# Electronics_Schematic.net
KiCad netlist of a schematic drawn in EAGLE
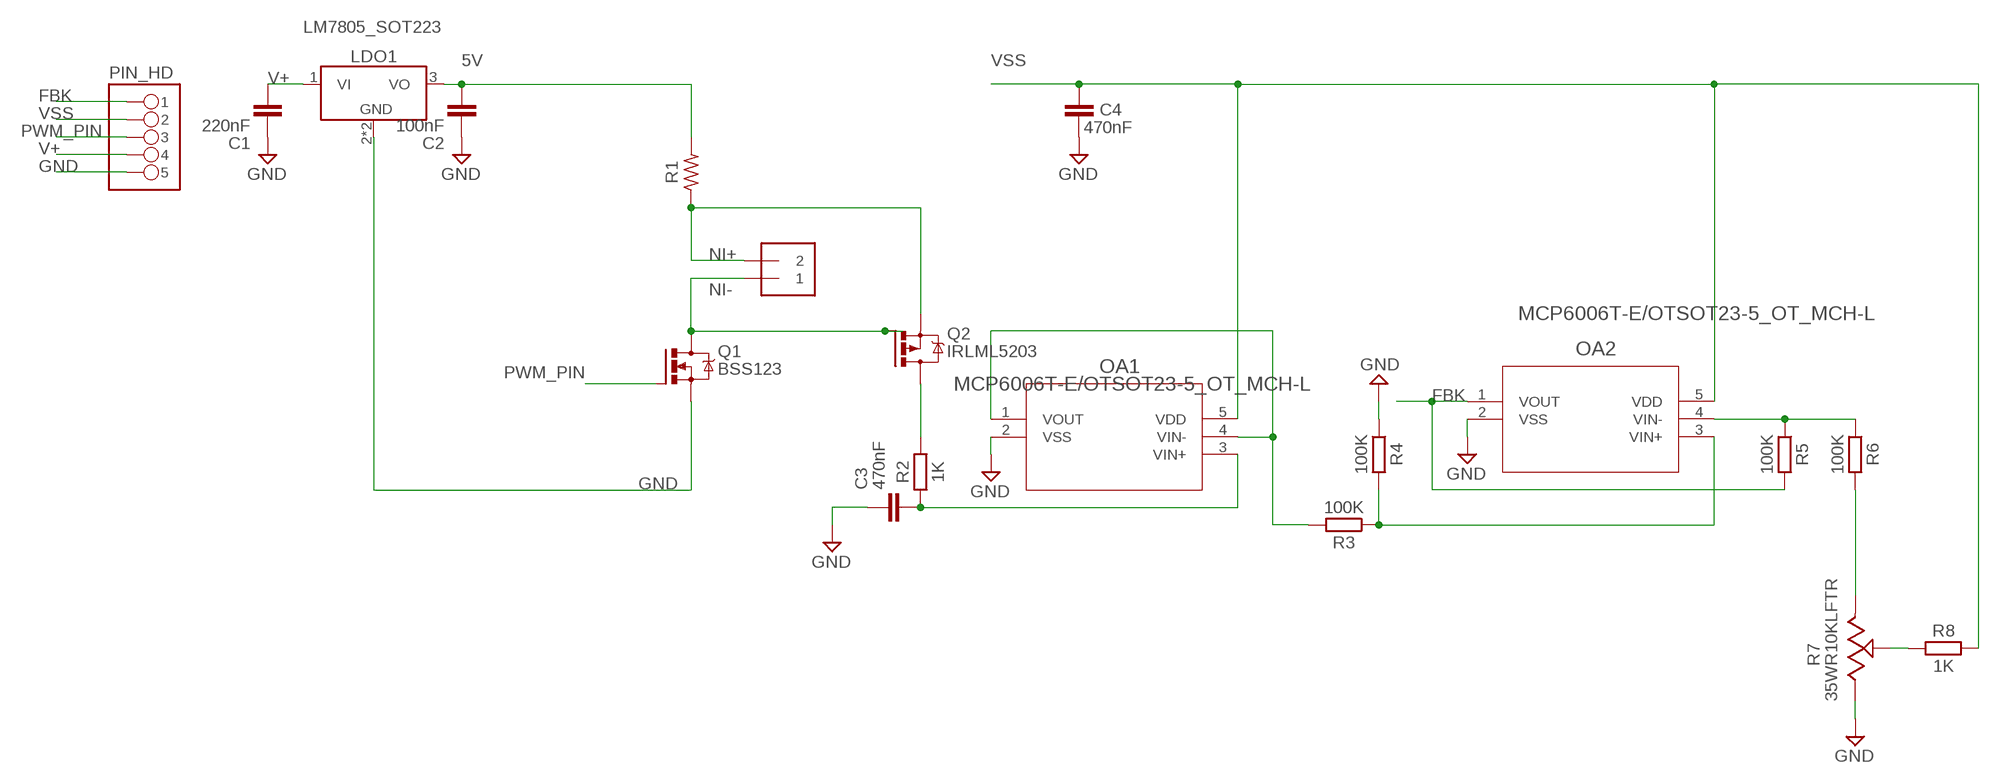
[diagram p0: schematic, sheet 1]

(export (version "E")
  (design (tool "Eeschema 10.0.6"))
  (components
    (comp (ref "C1")
      (value "220nF")
      (footprint "eagle-import:CAPC1005X60")
      (libsource (lib "eagle-import") (part "CCHIP-0402(1005-METRIC)_"))
    )
    (comp (ref "C2")
      (value "100nF")
      (footprint "eagle-import:CAPC1005X60")
      (libsource (lib "eagle-import") (part "CCHIP-0402(1005-METRIC)_"))
    )
    (comp (ref "C3")
      (value "470nF")
      (footprint "eagle-import:CAPC1005X60")
      (libsource (lib "eagle-import") (part "CCHIP-0402(1005-METRIC)_"))
    )
    (comp (ref "C4")
      (value "470nF")
      (footprint "eagle-import:CAPC1005X60")
      (libsource (lib "eagle-import") (part "CCHIP-0402(1005-METRIC)_"))
    )
    (comp (ref "LDO1")
      (value "LM7805_SOT223")
      (footprint "eagle-import:SOT230P700X170-4")
      (libsource (lib "eagle-import") (part "LM7805_SOT223"))
    )
    (comp (ref "NITI")
      (value "1X2-3.5MM")
      (footprint "eagle-import:1X2-3.5MM")
      (libsource (lib "eagle-import") (part "1X2-3.5MM"))
    )
    (comp (ref "OA1")
      (value "MCP6006T-E/OTSOT23-5_OT_MCH-L")
      (footprint "eagle-import:SOT23-5_OT_MCH-L")
      (fields
        (field (name "MANUFACTURER_PART_NUMBER") "MCP6006T-E/OT")
        (field (name "COPYRIGHT") "Copyright (C) 2024 Ultra Librarian. All rights reserved.")
      )
      (libsource (lib "eagle-import") (part "MCP6006T-E/OTSOT23-5_OT_MCH-L"))
    )
    (comp (ref "OA2")
      (value "MCP6006T-E/OTSOT23-5_OT_MCH-L")
      (footprint "eagle-import:SOT23-5_OT_MCH-L")
      (fields
        (field (name "MANUFACTURER_PART_NUMBER") "MCP6006T-E/OT")
        (field (name "COPYRIGHT") "Copyright (C) 2024 Ultra Librarian. All rights reserved.")
      )
      (libsource (lib "eagle-import") (part "MCP6006T-E/OTSOT23-5_OT_MCH-L"))
    )
    (comp (ref "PIN_HD")
      (value "PINHD-1X05_1X05M")
      (footprint "eagle-import:1X05")
      (libsource (lib "eagle-import") (part "PINHD-1X05_1X05M"))
    )
    (comp (ref "Q1")
      (value "BSS123")
      (footprint "eagle-import:SOT23")
      (fields (field (name "MANUFACTURER") "ON Semiconductor") (field (name "MPN") "BSS123L"))
      (libsource (lib "eagle-import") (part "NMOSFET__SOT23-GSDBSS123"))
    )
    (comp (ref "Q2")
      (value "IRLML5203")
      (footprint "eagle-import:SOT23")
      (fields (field (name "MANUFACTURER") "Infineon Technologies") (field (name "MPN") "IRLML5203TRPBF"))
      (libsource (lib "eagle-import") (part "PMOSFET__SOT23-GSDIRLML5203"))
    )
    (comp (ref "R1")
      (value "R-US_AXIAL-11.7MM-PITCH")
      (footprint "eagle-import:RESAD1176W63L850D250B")
      (libsource (lib "eagle-import") (part "R-USAXIAL-11.7MM-PITCH_"))
    )
    (comp (ref "R2")
      (value "1K")
      (footprint "eagle-import:RESC1005X40")
      (libsource (lib "eagle-import") (part "RCHIP-0402(1005-METRIC)_"))
    )
    (comp (ref "R3")
      (value "100K")
      (footprint "eagle-import:RESC1005X40")
      (libsource (lib "eagle-import") (part "RCHIP-0402(1005-METRIC)_"))
    )
    (comp (ref "R4")
      (value "100K")
      (footprint "eagle-import:RESC1005X40")
      (libsource (lib "eagle-import") (part "RCHIP-0402(1005-METRIC)_"))
    )
    (comp (ref "R5")
      (value "100K")
      (footprint "eagle-import:RESC1005X40")
      (libsource (lib "eagle-import") (part "RCHIP-0402(1005-METRIC)_"))
    )
    (comp (ref "R6")
      (value "100K")
      (footprint "eagle-import:RESC1005X40")
      (libsource (lib "eagle-import") (part "RCHIP-0402(1005-METRIC)_"))
    )
    (comp (ref "R7")
      (value "35WR10KLFTR")
      (footprint "eagle-import:TRIM_35WR10KLFTR")
      (fields (field (name "MANUFACTURER") "TT Electronics/BI"))
      (libsource (lib "eagle-import") (part "35WR10KLFTR"))
    )
    (comp (ref "R8")
      (value "1K")
      (footprint "eagle-import:RESC1005X40")
      (libsource (lib "eagle-import") (part "RCHIP-0402(1005-METRIC)_"))
    )
  )
  (nets
    (net (code "1") (name "/5V") (class "Default")
      (node (ref "C2") (pin "2") (pinfunction "2_2") (pintype "passive"))
      (node (ref "LDO1") (pin "3") (pinfunction "VO_3") (pintype "output"))
      (node (ref "R1") (pin "2") (pinfunction "2_2") (pintype "passive"))
    )
    (net (code "2") (name "/FBK") (class "Default")
      (node (ref "OA2") (pin "1") (pinfunction "VOUT_1") (pintype "output"))
      (node (ref "PIN_HD") (pin "1") (pinfunction "1_1") (pintype "bidirectional"))
      (node (ref "R5") (pin "2") (pinfunction "2_2") (pintype "passive"))
    )
    (net (code "3") (name "/NI+") (class "Default")
      (node (ref "NITI") (pin "2") (pinfunction "2_2") (pintype "passive"))
      (node (ref "Q2") (pin "2") (pinfunction "S_2") (pintype "passive"))
      (node (ref "R1") (pin "1") (pinfunction "1_1") (pintype "passive"))
    )
    (net (code "4") (name "/NI-") (class "Default")
      (node (ref "NITI") (pin "1") (pinfunction "1_1") (pintype "passive"))
      (node (ref "Q1") (pin "3") (pinfunction "D_3") (pintype "passive"))
      (node (ref "Q2") (pin "1") (pinfunction "G_1") (pintype "passive"))
    )
    (net (code "5") (name "/PWM_PIN") (class "Default")
      (node (ref "PIN_HD") (pin "3") (pinfunction "3_3") (pintype "bidirectional"))
      (node (ref "Q1") (pin "1") (pinfunction "G_1") (pintype "passive"))
    )
    (net (code "6") (name "/V+") (class "Default")
      (node (ref "C1") (pin "2") (pinfunction "2_2") (pintype "passive"))
      (node (ref "LDO1") (pin "1") (pinfunction "VI_1") (pintype "input"))
      (node (ref "PIN_HD") (pin "4") (pinfunction "4_4") (pintype "bidirectional"))
    )
    (net (code "7") (name "/VSS") (class "Default")
      (node (ref "C4") (pin "2") (pinfunction "2_2") (pintype "passive"))
      (node (ref "OA1") (pin "5") (pinfunction "VDD_5") (pintype "power_in"))
      (node (ref "OA2") (pin "5") (pinfunction "VDD_5") (pintype "power_in"))
      (node (ref "PIN_HD") (pin "2") (pinfunction "2_2") (pintype "bidirectional"))
      (node (ref "R8") (pin "2") (pinfunction "2_2") (pintype "passive"))
    )
    (net (code "8") (name "GND") (class "Default")
      (node (ref "C1") (pin "1") (pinfunction "1_1") (pintype "passive"))
      (node (ref "C2") (pin "1") (pinfunction "1_1") (pintype "passive"))
      (node (ref "C3") (pin "1") (pinfunction "1_1") (pintype "passive"))
      (node (ref "C4") (pin "1") (pinfunction "1_1") (pintype "passive"))
      (node (ref "LDO1") (pin "2") (pinfunction "GND_2") (pintype "passive"))
      (node (ref "LDO1") (pin "4") (pinfunction "GND_4") (pintype "passive"))
      (node (ref "OA1") (pin "2") (pinfunction "VSS_2") (pintype "passive"))
      (node (ref "OA2") (pin "2") (pinfunction "VSS_2") (pintype "passive"))
      (node (ref "PIN_HD") (pin "5") (pinfunction "5_5") (pintype "bidirectional"))
      (node (ref "Q1") (pin "2") (pinfunction "S_2") (pintype "passive"))
      (node (ref "R4") (pin "1") (pinfunction "1_1") (pintype "passive"))
      (node (ref "R7") (pin "1") (pinfunction "1_1") (pintype "passive"))
    )
    (net (code "9") (name "Net-(OA1-VIN+)") (class "Default")
      (node (ref "C3") (pin "2") (pinfunction "2_2") (pintype "passive"))
      (node (ref "OA1") (pin "3") (pinfunction "VIN+_3") (pintype "input"))
      (node (ref "R2") (pin "1") (pinfunction "1_1") (pintype "passive"))
    )
    (net (code "10") (name "Net-(OA1-VIN-)") (class "Default")
      (node (ref "OA1") (pin "1") (pinfunction "VOUT_1") (pintype "output"))
      (node (ref "OA1") (pin "4") (pinfunction "VIN-_4") (pintype "input"))
      (node (ref "R3") (pin "2") (pinfunction "2_2") (pintype "passive"))
    )
    (net (code "11") (name "Net-(OA2-VIN+)") (class "Default")
      (node (ref "OA2") (pin "3") (pinfunction "VIN+_3") (pintype "input"))
      (node (ref "R3") (pin "1") (pinfunction "1_1") (pintype "passive"))
      (node (ref "R4") (pin "2") (pinfunction "2_2") (pintype "passive"))
    )
    (net (code "12") (name "Net-(OA2-VIN-)") (class "Default")
      (node (ref "OA2") (pin "4") (pinfunction "VIN-_4") (pintype "input"))
      (node (ref "R5") (pin "1") (pinfunction "1_1") (pintype "passive"))
      (node (ref "R6") (pin "1") (pinfunction "1_1") (pintype "passive"))
    )
    (net (code "13") (name "Net-(Q2-D)") (class "Default")
      (node (ref "Q2") (pin "3") (pinfunction "D_3") (pintype "passive"))
      (node (ref "R2") (pin "2") (pinfunction "2_2") (pintype "passive"))
    )
    (net (code "14") (name "Net-(R6-Pad2)") (class "Default")
      (node (ref "R6") (pin "2") (pinfunction "2_2") (pintype "passive"))
      (node (ref "R7") (pin "3") (pinfunction "3_3") (pintype "passive"))
    )
    (net (code "15") (name "Net-(R7-Pad2)") (class "Default")
      (node (ref "R7") (pin "2") (pinfunction "2_2") (pintype "passive"))
      (node (ref "R8") (pin "1") (pinfunction "1_1") (pintype "passive"))
    )
  )
)
